# Power_Distribution.net
KiCad netlist of a schematic drawn in Altium Designer
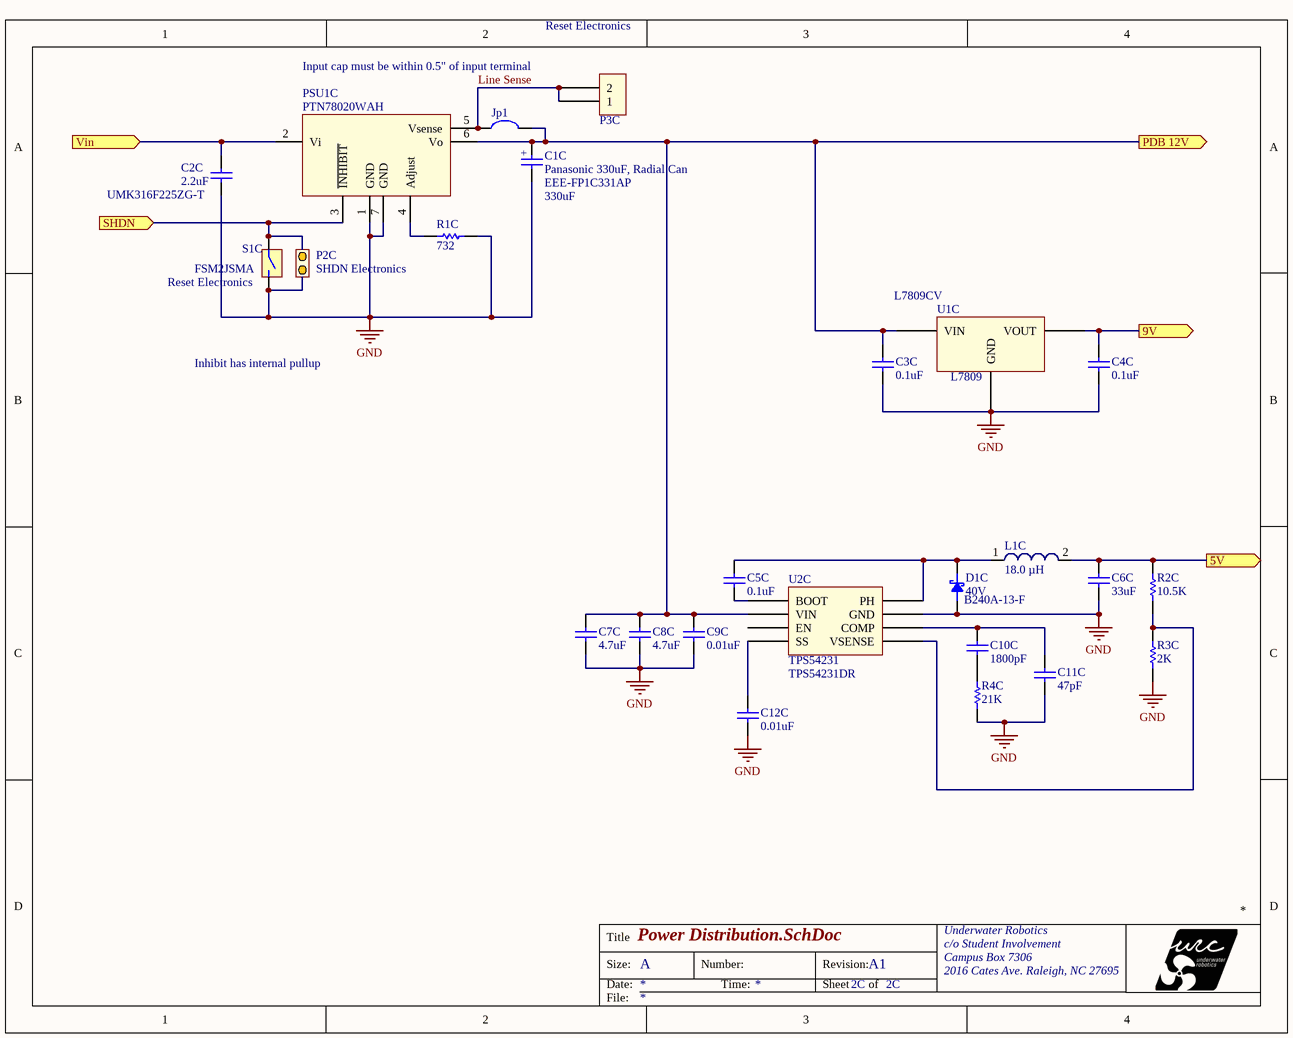
[diagram p0: Power Distribution.SchDoc]

(export (version "E")
  (design (tool "Eeschema 10.0.6"))
  (components
    (comp (ref "C1C")
      (value "Panasonic 330uF, Radial Can")
      (footprint "EEE-FP1C331AP")
      (description "Aluminum Radial Can, Panasonic, 330uF, 16V, SMD")
      (fields (field (name "MANUFACTURER PART NUMBER") "EEE-FP1C331AP") (field (name "ALTIUM_VALUE") "330uF"))
      (libsource (lib "Capacitors SchLib") (part "Panasonic 330uF, Radial Can"))
    )
    (comp (ref "C2C")
      (value "2.2uF")
      (footprint "C1206")
      (description "Ceramic MLCC, Taiyo Yuden, X7R Dielectric")
      (fields
        (field (name "MANUFACTURER PART NUMBER") "UMK316F225ZG-T")
        (field (name "Comment") "2.2uF, C1206 TY , Ceramic MLCC")
      )
      (libsource (lib "Capacitors SchLib") (part "2.2uF, C1206 TY , Ceramic MLCC"))
    )
    (comp (ref "C3C")
      (value "0.1uF")
      (footprint "C0603")
      (description "Ceramic MLCC, Multicompo, X7R Dielectric")
      (fields
        (field (name "MANUFACTURER PART NUMBER") "MC0603B104K500CT")
        (field (name "Comment") "0.1uF, C0603, MultiComp")
      )
      (libsource (lib "Capacitors SchLib") (part "0.1uF, C0603, MultiComp"))
    )
    (comp (ref "C4C")
      (value "0.1uF")
      (footprint "C0603")
      (description "Ceramic MLCC, Multicompo, X7R Dielectric")
      (fields
        (field (name "MANUFACTURER PART NUMBER") "MC0603B104K500CT")
        (field (name "Comment") "0.1uF, C0603, MultiComp")
      )
      (libsource (lib "Capacitors SchLib") (part "0.1uF, C0603, MultiComp"))
    )
    (comp (ref "C5C")
      (value "0.1uF")
      (footprint "C0603")
      (description "Ceramic MLCC, Multicompo, X7R Dielectric")
      (fields
        (field (name "MANUFACTURER PART NUMBER") "MC0603B104K500CT")
        (field (name "Comment") "0.1uF, C0603, MultiComp")
      )
      (libsource (lib "Capacitors SchLib") (part "0.1uF, C0603, MultiComp"))
    )
    (comp (ref "C6C")
      (value "33uF")
      (footprint "C1210")
      (description "Ceramic MLCC, TDK, X5R Dielectric")
      (fields
        (field (name "MANUFACTURER PART NUMBER") "C3225X5R0J336M250AA")
        (field (name "Comment") "33uF, 6.3V, C1210, TDK")
      )
      (libsource (lib "Capacitors SchLib") (part "33uF, 6.3V, C1210, TDK"))
    )
    (comp (ref "C7C")
      (value "4.7uF")
      (footprint "C0805")
      (description "Ceramic MLCC, Multicomp, X5R Dielectric")
      (fields
        (field (name "MANUFACTURER PART NUMBER") "MC0805X475M100CT")
        (field (name "Comment") "4.7uF, C0805, Multicomp")
      )
      (libsource (lib "Capacitors SchLib") (part "4.7uF, C0805, Multicomp"))
    )
    (comp (ref "C8C")
      (value "4.7uF")
      (footprint "C0805")
      (description "Ceramic MLCC, Multicomp, X5R Dielectric")
      (fields
        (field (name "MANUFACTURER PART NUMBER") "MC0805X475M100CT")
        (field (name "Comment") "4.7uF, C0805, Multicomp")
      )
      (libsource (lib "Capacitors SchLib") (part "4.7uF, C0805, Multicomp"))
    )
    (comp (ref "C9C")
      (value "0.01uF")
      (footprint "C0603")
      (description "Ceramic MLCC, AVX, X7R Dielectric")
      (fields
        (field (name "MANUFACTURER PART NUMBER") "06035C103KAT2A")
        (field (name "Comment") "0.01uF, C0603, AVX")
      )
      (libsource (lib "Capacitors SchLib") (part "0.01uF, C0603, AVX"))
    )
    (comp (ref "C10C")
      (value "1800pF")
      (footprint "C0603")
      (description "Ceramic MLCC, Multicomp, X7R Dielectric")
      (fields
        (field (name "MANUFACTURER PART NUMBER") "MC0603B182K500CT")
        (field (name "Comment") "1800pF, 50V, C0603, Multicomp")
      )
      (libsource (lib "Capacitors SchLib") (part "1800pF, 50V, C0603, Multicomp"))
    )
    (comp (ref "C11C")
      (value "47pF")
      (footprint "C0402")
      (description "Ceramic MLCC, Yageo, C0G/NP0 Dielectric")
      (fields
        (field (name "MANUFACTURER PART NUMBER") "CC0402JRNPO9BN470")
        (field (name "Comment") "47pF, 50V, C0402, Yageo")
      )
      (libsource (lib "Capacitors SchLib") (part "47pF, 50V, C0402, Yageo"))
    )
    (comp (ref "C12C")
      (value "0.01uF")
      (footprint "C0603")
      (description "Ceramic MLCC, AVX, X7R Dielectric")
      (fields
        (field (name "MANUFACTURER PART NUMBER") "06035C103KAT2A")
        (field (name "Comment") "0.01uF, C0603, AVX")
      )
      (libsource (lib "Capacitors SchLib") (part "0.01uF, C0603, AVX"))
    )
    (comp (ref "D1C")
      (value "40V")
      (footprint "SCHOTTKY-B220/A")
      (fields
        (field (name "MANUFACTURER") "MULTICOMP")
        (field (name "MANUFACTURER PART NUMBER") "B240A-13-F")
        (field (name "Comment") "Shottky")
      )
      (libsource (lib "URC") (part "Schottky"))
    )
    (comp (ref "Jp1")
      (value "Jumper")
      (footprint "Jumper (optional) SMD")
      (description "Resistor")
      (libsource (lib "URC") (part "Jump Optional"))
    )
    (comp (ref "L1C")
      (value "18.0 µH")
      (footprint "WE-PD 1245")
      (description "SMD-Shielded Power Inductor WE-PD, L=18.0 µH")
      (fields (field (name "MANUFACTURER PART NUMBER") "7447715180"))
      (libsource (lib "WE-PD_rev15b") (part "WE-PD 1245, LS, 7447715180"))
    )
    (comp (ref "P2C")
      (value "Header")
      (footprint "1x2 Header")
      (description "1x2 Header")
      (libsource (lib "URC") (part "1x2 Header"))
    )
    (comp (ref "P3C")
      (value "Header")
      (footprint "1x2 Header")
      (description "1x2 Header")
      (libsource (lib "") (part "1x2 Header_1"))
    )
    (comp (ref "PSU1C")
      (value "PTN78020W")
      (footprint "PTN78020")
      (description "Adjustable, non-isolating DC-DC converter")
      (fields
        (field (name "MANUFACTURER") "TEXAS INSTRUMENTS")
        (field (name "MANUFACTURER PART NUMBER") "PTN78020WAH")
      )
      (libsource (lib "URC") (part "PTN78020W"))
    )
    (comp (ref "R1C")
      (value "732")
      (footprint "R0402")
      (description "Resistor")
      (fields (field (name "TOLERANCE") "1%") (field (name "MANUFACTURER PART NUMBER") "ERJ-2RKF7320X"))
      (libsource (lib "Resistors SchLib") (part "732, 1%, 100mW, Panasonic, R0402"))
    )
    (comp (ref "R2C")
      (value "10.5K")
      (footprint "R0603")
      (description "Resistor")
      (fields (field (name "TOLERANCE") "1%") (field (name "MANUFACTURER PART NUMBER") "MC0063W0603110K5"))
      (libsource (lib "Resistors SchLib") (part "10.5K, 1%, 63mW, Multicomp, R0603"))
    )
    (comp (ref "R3C")
      (value "2K")
      (footprint "R0603")
      (description "Resistor")
      (fields (field (name "TOLERANCE") "1%") (field (name "MANUFACTURER PART NUMBER") "RC0603FR-072KL"))
      (libsource (lib "Resistors SchLib") (part "2k, 1%, 100mW, Yageo, R0603"))
    )
    (comp (ref "R4C")
      (value "21K")
      (footprint "R0603")
      (description "Resistor")
      (fields (field (name "TOLERANCE") "1%") (field (name "MANUFACTURER PART NUMBER") "CRCW060321K0FKEA"))
      (libsource (lib "Resistors SchLib") (part "21K, 1%, 100mW, Vishay, R0603"))
    )
    (comp (ref "S1C")
      (value "FSM2JSMA")
      (footprint "FSM2JSMA")
      (description "Tactile Switch (OFF-MOM)")
      (libsource (lib "URC") (part "FSM2JSMA"))
    )
    (comp (ref "U1C")
      (value "L7809")
      (footprint "L7809CD2T-D2PAK")
      (fields
        (field (name "MANUFACTURER") "STMICROELECTRONICS")
        (field (name "MANUFACTURER PART NUMBER") "L7809CV")
      )
      (libsource (lib "URC") (part "L7809"))
    )
    (comp (ref "U2C")
      (value "TPS54231")
      (footprint "TPS54231-SOIC8")
      (description "2A Switching Regulator")
      (fields
        (field (name "MANUFACTURER") "TEXAS INSTRUMENTS")
        (field (name "MANUFACTURER PART NUMBER") "TPS54231DR")
      )
      (libsource (lib "URC") (part "TPS54231"))
    )
  )
  (nets
    (net (code "1") (name "/5V") (class "Default")
      (node (ref "C6C") (pin "1") (pinfunction "+_1") (pintype "passive"))
      (node (ref "L1C") (pin "2") (pinfunction "2_2") (pintype "passive"))
      (node (ref "R2C") (pin "2") (pinfunction "2_2") (pintype "passive"))
    )
    (net (code "2") (name "/9V") (class "Default")
      (node (ref "C4C") (pin "1") (pinfunction "+_1") (pintype "passive"))
      (node (ref "U1C") (pin "OUTPUT") (pinfunction "VOUT_OUTPUT") (pintype "passive"))
    )
    (net (code "3") (name "/Line Sense") (class "Default")
      (node (ref "Jp1") (pin "1") (pinfunction "1_1") (pintype "passive"))
      (node (ref "P3C") (pin "1") (pinfunction "1_1") (pintype "passive"))
      (node (ref "P3C") (pin "2") (pinfunction "2_2") (pintype "passive"))
      (node (ref "PSU1C") (pin "5") (pinfunction "Vsense_5") (pintype "passive"))
    )
    (net (code "4") (name "/PDB 12V") (class "Default")
      (node (ref "C1C") (pin "1") (pinfunction "+_1") (pintype "passive"))
      (node (ref "C3C") (pin "1") (pinfunction "+_1") (pintype "passive"))
      (node (ref "C7C") (pin "1") (pinfunction "+_1") (pintype "passive"))
      (node (ref "C8C") (pin "1") (pinfunction "+_1") (pintype "passive"))
      (node (ref "C9C") (pin "1") (pinfunction "+_1") (pintype "passive"))
      (node (ref "Jp1") (pin "2") (pinfunction "2_2") (pintype "passive"))
      (node (ref "PSU1C") (pin "6") (pinfunction "Vo_6") (pintype "passive"))
      (node (ref "U1C") (pin "INPUT") (pinfunction "VIN_INPUT") (pintype "passive"))
      (node (ref "U2C") (pin "VIN") (pinfunction "VIN_VIN") (pintype "passive"))
    )
    (net (code "5") (name "/SHDN") (class "Default")
      (node (ref "P2C") (pin "1") (pinfunction "1_1") (pintype "passive"))
      (node (ref "PSU1C") (pin "3") (pinfunction "~{INHIBIT}_3") (pintype "passive"))
      (node (ref "S1C") (pin "1") (pinfunction "1_1") (pintype "passive"))
      (node (ref "S1C") (pin "2") (pinfunction "2_2") (pintype "passive"))
    )
    (net (code "6") (name "/Vin") (class "Default")
      (node (ref "C2C") (pin "1") (pinfunction "+_1") (pintype "passive"))
      (node (ref "PSU1C") (pin "2") (pinfunction "Vi_2") (pintype "passive"))
    )
    (net (code "7") (name "GND") (class "Default")
      (node (ref "C11C") (pin "2") (pinfunction "2_2") (pintype "passive"))
      (node (ref "C12C") (pin "2") (pinfunction "2_2") (pintype "passive"))
      (node (ref "C1C") (pin "2") (pinfunction "2_2") (pintype "passive"))
      (node (ref "C2C") (pin "2") (pinfunction "2_2") (pintype "passive"))
      (node (ref "C3C") (pin "2") (pinfunction "2_2") (pintype "passive"))
      (node (ref "C4C") (pin "2") (pinfunction "2_2") (pintype "passive"))
      (node (ref "C6C") (pin "2") (pinfunction "2_2") (pintype "passive"))
      (node (ref "C7C") (pin "2") (pinfunction "2_2") (pintype "passive"))
      (node (ref "C8C") (pin "2") (pinfunction "2_2") (pintype "passive"))
      (node (ref "C9C") (pin "2") (pinfunction "2_2") (pintype "passive"))
      (node (ref "D1C") (pin "2") (pinfunction "2_2") (pintype "passive"))
      (node (ref "P2C") (pin "2") (pinfunction "2_2") (pintype "passive"))
      (node (ref "PSU1C") (pin "1") (pinfunction "GND_1") (pintype "passive"))
      (node (ref "PSU1C") (pin "7") (pinfunction "GND_7") (pintype "passive"))
      (node (ref "R1C") (pin "2") (pinfunction "2_2") (pintype "passive"))
      (node (ref "R3C") (pin "1") (pinfunction "1_1") (pintype "passive"))
      (node (ref "R4C") (pin "1") (pinfunction "1_1") (pintype "passive"))
      (node (ref "S1C") (pin "3") (pinfunction "3_3") (pintype "passive"))
      (node (ref "S1C") (pin "4") (pinfunction "4_4") (pintype "passive"))
      (node (ref "U1C") (pin "GND") (pinfunction "GND_GND") (pintype "passive"))
      (node (ref "U2C") (pin "GND") (pinfunction "GND_GND") (pintype "passive"))
    )
    (net (code "8") (name "Net-(C5C-+)") (class "Default")
      (node (ref "C5C") (pin "1") (pinfunction "+_1") (pintype "passive"))
      (node (ref "D1C") (pin "1") (pinfunction "1_1") (pintype "passive"))
      (node (ref "L1C") (pin "1") (pinfunction "1_1") (pintype "passive"))
      (node (ref "U2C") (pin "PH") (pinfunction "PH_PH") (pintype "passive"))
    )
    (net (code "9") (name "Net-(C5C-Pad2)") (class "Default")
      (node (ref "C5C") (pin "2") (pinfunction "2_2") (pintype "passive"))
      (node (ref "U2C") (pin "BOOT") (pinfunction "BOOT_BOOT") (pintype "passive"))
    )
    (net (code "10") (name "Net-(C10C-+)") (class "Default")
      (node (ref "C10C") (pin "1") (pinfunction "+_1") (pintype "passive"))
      (node (ref "C11C") (pin "1") (pinfunction "+_1") (pintype "passive"))
      (node (ref "U2C") (pin "COMP") (pinfunction "COMP_COMP") (pintype "passive"))
    )
    (net (code "11") (name "Net-(C10C-Pad2)") (class "Default")
      (node (ref "C10C") (pin "2") (pinfunction "2_2") (pintype "passive"))
      (node (ref "R4C") (pin "2") (pinfunction "2_2") (pintype "passive"))
    )
    (net (code "12") (name "Net-(C12C-+)") (class "Default")
      (node (ref "C12C") (pin "1") (pinfunction "+_1") (pintype "passive"))
      (node (ref "U2C") (pin "SS") (pinfunction "SS_SS") (pintype "passive"))
    )
    (net (code "13") (name "Net-(PSU1C-Adjust)") (class "Default")
      (node (ref "PSU1C") (pin "4") (pinfunction "Adjust_4") (pintype "passive"))
      (node (ref "R1C") (pin "1") (pinfunction "1_1") (pintype "passive"))
    )
    (net (code "14") (name "Net-(R2C-Pad1)") (class "Default")
      (node (ref "R2C") (pin "1") (pinfunction "1_1") (pintype "passive"))
      (node (ref "R3C") (pin "2") (pinfunction "2_2") (pintype "passive"))
      (node (ref "U2C") (pin "VSENSE") (pinfunction "VSENSE_VSENSE") (pintype "passive"))
    )
    (net (code "15") (name "unconnected-(U2C-PadEN)") (class "Default")
      (node (ref "U2C") (pin "EN") (pinfunction "EN_EN") (pintype "passive"))
    )
  )
)
